# pc_to_pc_communication.net
KiCad netlist of a schematic drawn in EAGLE
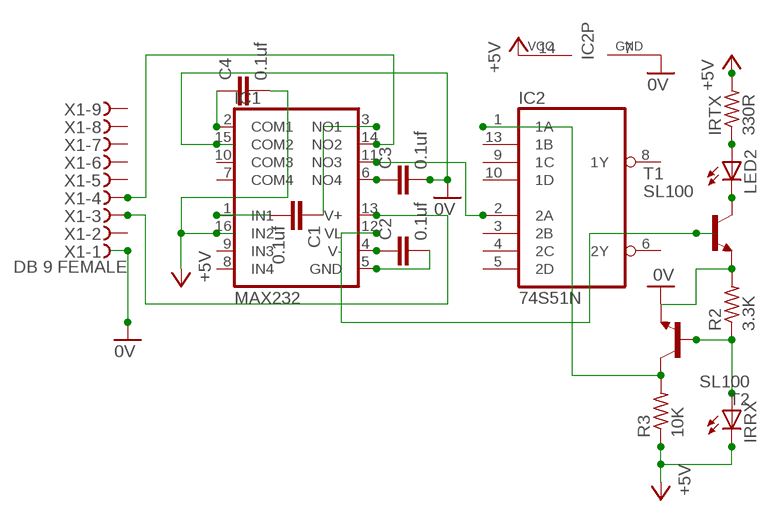
[diagram p0: schematic, sheet 1]

(export (version "E")
  (design (tool "Eeschema 10.0.6"))
  (components
    (comp (ref "C1")
      (value "0.1uf")
      (footprint "eagle-import:C2.5-3")
      (libsource (lib "eagle-import") (part "C2,5-3"))
    )
    (comp (ref "C2")
      (value "0.1uf")
      (footprint "eagle-import:C2.5-3")
      (libsource (lib "eagle-import") (part "C2,5-3"))
    )
    (comp (ref "C3")
      (value "0.1uf")
      (footprint "eagle-import:C2.5-3")
      (libsource (lib "eagle-import") (part "C2,5-3"))
    )
    (comp (ref "C4")
      (value "0.1uf")
      (footprint "eagle-import:C2.5-3")
      (libsource (lib "eagle-import") (part "C2,5-3"))
    )
    (comp (ref "IC1")
      (value "MAX232")
      (footprint "eagle-import:DIL16")
      (fields (field (name "MPN") "MAX313EPE+"))
      (libsource (lib "eagle-import") (part "MAX313PEE"))
    )
    (comp (ref "IC2")
      (value "74S51N")
      (footprint "eagle-import:DIL14")
      (libsource (lib "eagle-import") (part "74S51N"))
    )
    (comp (ref "IRRX")
      (value "LED3MM")
      (footprint "eagle-import:LED3MM")
      (libsource (lib "eagle-import") (part "LED3MM"))
    )
    (comp (ref "IRTX")
      (value "330R")
      (footprint "eagle-import:0204_7")
      (libsource (lib "eagle-import") (part "R-US_0204/7"))
    )
    (comp (ref "LED2")
      (value "LED3MM")
      (footprint "eagle-import:LED3MM")
      (libsource (lib "eagle-import") (part "LED3MM"))
    )
    (comp (ref "R2")
      (value "3.3K")
      (footprint "eagle-import:0204_7")
      (libsource (lib "eagle-import") (part "R-US_0204/7"))
    )
    (comp (ref "R3")
      (value "10K")
      (footprint "eagle-import:0204_7")
      (libsource (lib "eagle-import") (part "R-US_0204/7"))
    )
    (comp (ref "T1")
      (value "SL100")
      (footprint "eagle-import:TO5")
      (libsource (lib "eagle-import") (part "2N2102"))
    )
    (comp (ref "T2")
      (value "SL100")
      (footprint "eagle-import:TO5")
      (libsource (lib "eagle-import") (part "2N2102"))
    )
    (comp (ref "X1")
      (value "DB 9 FEMALE")
      (footprint "eagle-import:H2M09ST")
      (libsource (lib "eagle-import") (part "D-SUB9-H2M09ST"))
    )
  )
  (nets
    (net (code "1") (name "+5V") (class "Default")
      (node (ref "C4") (pin "2") (pinfunction "2_2") (pintype "passive"))
      (node (ref "IC1") (pin "16") (pinfunction "IN2_16") (pintype "input"))
      (node (ref "IC2") (pin "14") (pinfunction "VCC_14") (pintype "power_in"))
      (node (ref "IRRX") (pin "K") (pinfunction "C_K") (pintype "passive"))
      (node (ref "IRTX") (pin "2") (pinfunction "2_2") (pintype "passive"))
      (node (ref "R3") (pin "1") (pinfunction "1_1") (pintype "passive"))
    )
    (net (code "2") (name "0V") (class "Default")
      (node (ref "C3") (pin "2") (pinfunction "2_2") (pintype "passive"))
      (node (ref "IC1") (pin "15") (pinfunction "COM2_15") (pintype "passive"))
      (node (ref "IC2") (pin "7") (pinfunction "GND_7") (pintype "power_in"))
      (node (ref "R2") (pin "2") (pinfunction "2_2") (pintype "passive"))
      (node (ref "T1") (pin "1") (pinfunction "E_1") (pintype "passive"))
      (node (ref "T2") (pin "1") (pinfunction "E_1") (pintype "passive"))
      (node (ref "X1") (pin "1") (pinfunction "F_1") (pintype "passive"))
    )
    (net (code "3") (name "Net-(IC1-COM1)") (class "Default")
      (node (ref "C4") (pin "1") (pinfunction "1_1") (pintype "passive"))
      (node (ref "IC1") (pin "2") (pinfunction "COM1_2") (pintype "passive"))
    )
    (net (code "4") (name "Net-(IC1-GND)") (class "Default")
      (node (ref "C2") (pin "2") (pinfunction "2_2") (pintype "passive"))
      (node (ref "IC1") (pin "5") (pinfunction "GND_5") (pintype "power_in"))
    )
    (net (code "5") (name "Net-(IC1-IN1)") (class "Default")
      (node (ref "C1") (pin "2") (pinfunction "2_2") (pintype "passive"))
      (node (ref "IC1") (pin "1") (pinfunction "IN1_1") (pintype "input"))
    )
    (net (code "6") (name "Net-(IC1-NO1)") (class "Default")
      (node (ref "C1") (pin "1") (pinfunction "1_1") (pintype "passive"))
      (node (ref "IC1") (pin "3") (pinfunction "NO1_3") (pintype "passive"))
    )
    (net (code "7") (name "Net-(IC1-NO2)") (class "Default")
      (node (ref "IC1") (pin "14") (pinfunction "NO2_14") (pintype "passive"))
      (node (ref "X1") (pin "4") (pinfunction "F_4") (pintype "passive"))
    )
    (net (code "8") (name "Net-(IC1-NO3)") (class "Default")
      (node (ref "IC1") (pin "11") (pinfunction "NO3_11") (pintype "passive"))
      (node (ref "IC2") (pin "2") (pinfunction "2A_2") (pintype "input"))
    )
    (net (code "9") (name "Net-(IC1-NO4)") (class "Default")
      (node (ref "C3") (pin "1") (pinfunction "1_1") (pintype "passive"))
      (node (ref "IC1") (pin "6") (pinfunction "NO4_6") (pintype "passive"))
    )
    (net (code "10") (name "Net-(IC1-V+)") (class "Default")
      (node (ref "IC1") (pin "13") (pinfunction "V+_13") (pintype "power_in"))
      (node (ref "X1") (pin "3") (pinfunction "F_3") (pintype "passive"))
    )
    (net (code "11") (name "Net-(IC1-V-)") (class "Default")
      (node (ref "C2") (pin "1") (pinfunction "1_1") (pintype "passive"))
      (node (ref "IC1") (pin "4") (pinfunction "V-_4") (pintype "power_in"))
    )
    (net (code "12") (name "Net-(IC1-VL)") (class "Default")
      (node (ref "IC1") (pin "12") (pinfunction "VL_12") (pintype "power_in"))
      (node (ref "T1") (pin "2") (pinfunction "B_2") (pintype "passive"))
    )
    (net (code "13") (name "Net-(IC2A-1A)") (class "Default")
      (node (ref "IC2") (pin "1") (pinfunction "1A_1") (pintype "input"))
      (node (ref "R3") (pin "2") (pinfunction "2_2") (pintype "passive"))
      (node (ref "T2") (pin "3") (pinfunction "C_3") (pintype "passive"))
    )
    (net (code "14") (name "Net-(IRTX-Pad1)") (class "Default")
      (node (ref "IRTX") (pin "1") (pinfunction "1_1") (pintype "passive"))
      (node (ref "LED2") (pin "A") (pinfunction "A_A") (pintype "passive"))
    )
    (net (code "15") (name "Net-(LED2-C)") (class "Default")
      (node (ref "LED2") (pin "K") (pinfunction "C_K") (pintype "passive"))
      (node (ref "T1") (pin "3") (pinfunction "C_3") (pintype "passive"))
    )
    (net (code "16") (name "Net-(T2-B)") (class "Default")
      (node (ref "IRRX") (pin "A") (pinfunction "A_A") (pintype "passive"))
      (node (ref "R2") (pin "1") (pinfunction "1_1") (pintype "passive"))
      (node (ref "T2") (pin "2") (pinfunction "B_2") (pintype "passive"))
    )
    (net (code "17") (name "unconnected-(IC1-COM3-Pad10)") (class "Default")
      (node (ref "IC1") (pin "10") (pinfunction "COM3_10") (pintype "passive"))
    )
    (net (code "18") (name "unconnected-(IC1-COM4-Pad7)") (class "Default")
      (node (ref "IC1") (pin "7") (pinfunction "COM4_7") (pintype "passive"))
    )
    (net (code "19") (name "unconnected-(IC1-IN3-Pad9)") (class "Default")
      (node (ref "IC1") (pin "9") (pinfunction "IN3_9") (pintype "input"))
    )
    (net (code "20") (name "unconnected-(IC1-IN4-Pad8)") (class "Default")
      (node (ref "IC1") (pin "8") (pinfunction "IN4_8") (pintype "input"))
    )
    (net (code "21") (name "unconnected-(IC2A-1B-Pad13)") (class "Default")
      (node (ref "IC2") (pin "13") (pinfunction "1B_13") (pintype "input"))
    )
    (net (code "22") (name "unconnected-(IC2A-1C-Pad9)") (class "Default")
      (node (ref "IC2") (pin "9") (pinfunction "1C_9") (pintype "input"))
    )
    (net (code "23") (name "unconnected-(IC2A-1D-Pad10)") (class "Default")
      (node (ref "IC2") (pin "10") (pinfunction "1D_10") (pintype "input"))
    )
    (net (code "24") (name "unconnected-(IC2A-1Y-Pad8)") (class "Default")
      (node (ref "IC2") (pin "8") (pinfunction "1Y_8") (pintype "output"))
    )
    (net (code "25") (name "unconnected-(IC2A-2B-Pad3)") (class "Default")
      (node (ref "IC2") (pin "3") (pinfunction "2B_3") (pintype "input"))
    )
    (net (code "26") (name "unconnected-(IC2A-2C-Pad4)") (class "Default")
      (node (ref "IC2") (pin "4") (pinfunction "2C_4") (pintype "input"))
    )
    (net (code "27") (name "unconnected-(IC2A-2D-Pad5)") (class "Default")
      (node (ref "IC2") (pin "5") (pinfunction "2D_5") (pintype "input"))
    )
    (net (code "28") (name "unconnected-(IC2A-2Y-Pad6)") (class "Default")
      (node (ref "IC2") (pin "6") (pinfunction "2Y_6") (pintype "output"))
    )
    (net (code "29") (name "unconnected-(X1B-F-Pad2)") (class "Default")
      (node (ref "X1") (pin "2") (pinfunction "F_2") (pintype "passive"))
    )
    (net (code "30") (name "unconnected-(X1E-F-Pad5)") (class "Default")
      (node (ref "X1") (pin "5") (pinfunction "F_5") (pintype "passive"))
    )
    (net (code "31") (name "unconnected-(X1F-F-Pad6)") (class "Default")
      (node (ref "X1") (pin "6") (pinfunction "F_6") (pintype "passive"))
    )
    (net (code "32") (name "unconnected-(X1G-F-Pad7)") (class "Default")
      (node (ref "X1") (pin "7") (pinfunction "F_7") (pintype "passive"))
    )
    (net (code "33") (name "unconnected-(X1H-F-Pad8)") (class "Default")
      (node (ref "X1") (pin "8") (pinfunction "F_8") (pintype "passive"))
    )
    (net (code "34") (name "unconnected-(X1I-F-Pad9)") (class "Default")
      (node (ref "X1") (pin "9") (pinfunction "F_9") (pintype "passive"))
    )
  )
)
